# smartbedlight2.net
KiCad netlist of a schematic drawn in EAGLE
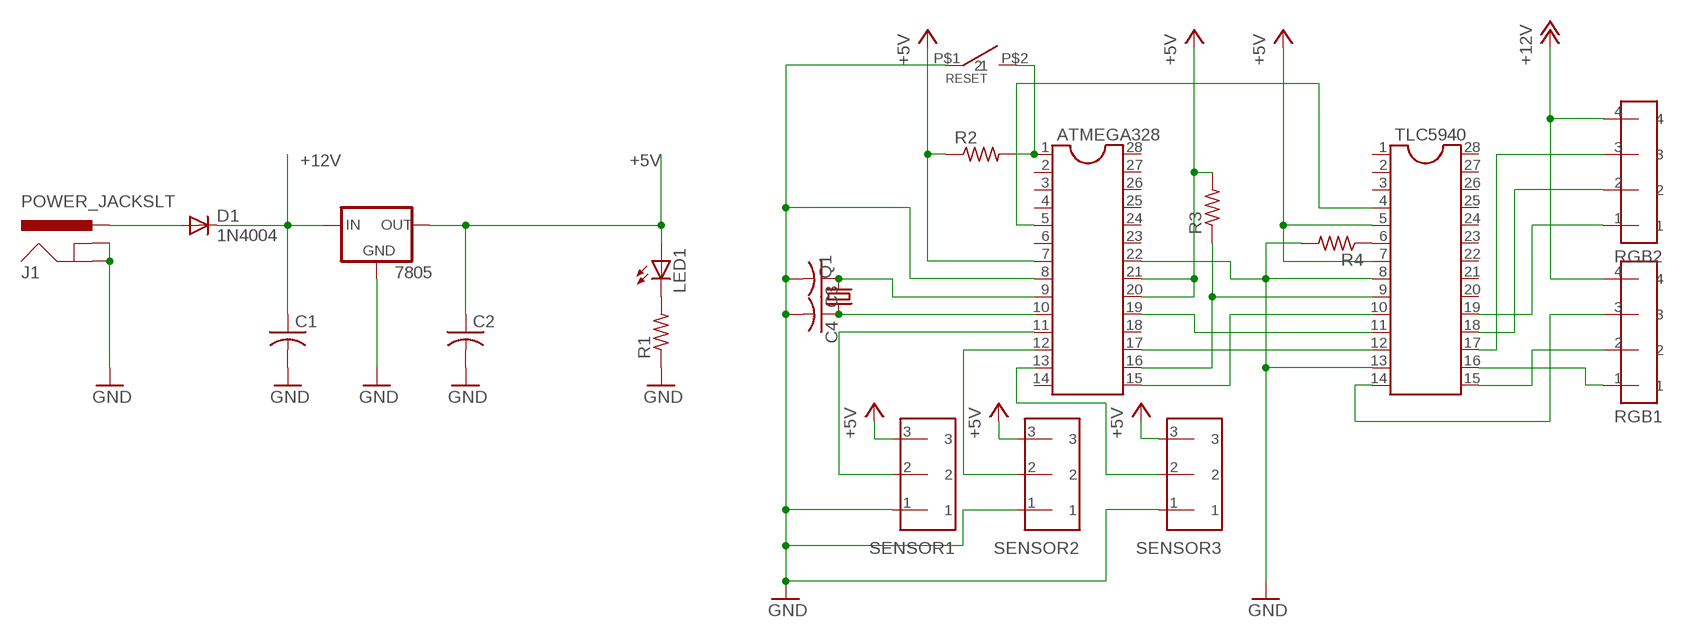
[diagram p0: schematic, sheet 1]

(export (version "E")
  (design (tool "Eeschema 10.0.6"))
  (components
    (comp (ref "7805")
      (value "V_REG_78XXSIDE")
      (footprint "eagle-import:78XXL")
      (libsource (lib "eagle-import") (part "V_REG_78XXSIDE"))
    )
    (comp (ref "ATMEGA328")
      (value "DIL28-3")
      (footprint "eagle-import:DIL28-3")
      (libsource (lib "eagle-import") (part "DIL28-3"))
    )
    (comp (ref "C1")
      (value "C-US025-030X050")
      (footprint "eagle-import:C025-030X050")
      (libsource (lib "eagle-import") (part "C-US025-030X050"))
    )
    (comp (ref "C2")
      (value "C-US025-030X050")
      (footprint "eagle-import:C025-030X050")
      (libsource (lib "eagle-import") (part "C-US025-030X050"))
    )
    (comp (ref "C3")
      (value "C-US025-025X050")
      (footprint "eagle-import:C025-025X050")
      (libsource (lib "eagle-import") (part "resistor_C-US025-025X050"))
    )
    (comp (ref "C4")
      (value "C-US025-025X050")
      (footprint "eagle-import:C025-025X050")
      (libsource (lib "eagle-import") (part "resistor_C-US025-025X050"))
    )
    (comp (ref "D1")
      (value "1N4004")
      (footprint "eagle-import:DO41-10")
      (libsource (lib "eagle-import") (part "1N4004"))
    )
    (comp (ref "J1")
      (value "POWER_JACKSLT")
      (footprint "eagle-import:POWER_JACK_SLOT")
      (libsource (lib "eagle-import") (part "POWER_JACKSLT"))
    )
    (comp (ref "LED1")
      (value "LED5MM")
      (footprint "eagle-import:LED5MM")
      (libsource (lib "eagle-import") (part "LED5MM"))
    )
    (comp (ref "Q1")
      (value "CRYSTALHC49U-V")
      (footprint "eagle-import:HC49U-V")
      (libsource (lib "eagle-import") (part "CRYSTALHC49U-V"))
    )
    (comp (ref "R1")
      (value "R-US_0204/7")
      (footprint "eagle-import:0204_7")
      (libsource (lib "eagle-import") (part "R-US_0204/7"))
    )
    (comp (ref "R2")
      (value "R-US_0207/10")
      (footprint "eagle-import:0207_10")
      (libsource (lib "eagle-import") (part "resistor_R-US_0207/10"))
    )
    (comp (ref "R3")
      (value "R-US_0207/10")
      (footprint "eagle-import:0207_10")
      (libsource (lib "eagle-import") (part "resistor_R-US_0207/10"))
    )
    (comp (ref "R4")
      (value "R-US_0207/10")
      (footprint "eagle-import:0207_10")
      (libsource (lib "eagle-import") (part "resistor_R-US_0207/10"))
    )
    (comp (ref "RESET")
      (value "TACK_SWITCH")
      (footprint "eagle-import:TACK_SWITCH")
      (libsource (lib "eagle-import") (part "TACK_SWITCH"))
    )
    (comp (ref "RGB1")
      (value "PINHEAD4")
      (footprint "eagle-import:PINHEAD4")
      (libsource (lib "eagle-import") (part "PINHEAD4"))
    )
    (comp (ref "RGB2")
      (value "PINHEAD4")
      (footprint "eagle-import:PINHEAD4")
      (libsource (lib "eagle-import") (part "PINHEAD4"))
    )
    (comp (ref "SENSOR1")
      (value "PINHEAD3")
      (footprint "eagle-import:PINHEAD")
      (libsource (lib "eagle-import") (part "PINHEAD3"))
    )
    (comp (ref "SENSOR2")
      (value "PINHEAD3")
      (footprint "eagle-import:PINHEAD")
      (libsource (lib "eagle-import") (part "PINHEAD3"))
    )
    (comp (ref "SENSOR3")
      (value "PINHEAD3")
      (footprint "eagle-import:PINHEAD")
      (libsource (lib "eagle-import") (part "PINHEAD3"))
    )
    (comp (ref "TLC5940")
      (value "DIL28-3")
      (footprint "eagle-import:DIL28-3")
      (libsource (lib "eagle-import") (part "DIL28-3"))
    )
  )
  (nets
    (net (code "1") (name "+5V") (class "Default")
      (node (ref "7805") (pin "OUT") (pinfunction "OUT_OUT") (pintype "output"))
      (node (ref "ATMEGA328") (pin "20") (pinfunction "20_20") (pintype "passive"))
      (node (ref "ATMEGA328") (pin "21") (pinfunction "21_21") (pintype "passive"))
      (node (ref "ATMEGA328") (pin "7") (pinfunction "7_7") (pintype "passive"))
      (node (ref "C2") (pin "1") (pinfunction "1_1") (pintype "passive"))
      (node (ref "LED1") (pin "A") (pinfunction "A_A") (pintype "passive"))
      (node (ref "R2") (pin "1") (pinfunction "1_1") (pintype "passive"))
      (node (ref "R3") (pin "2") (pinfunction "2_2") (pintype "passive"))
      (node (ref "SENSOR1") (pin "3") (pinfunction "3_3") (pintype "bidirectional"))
      (node (ref "SENSOR2") (pin "3") (pinfunction "3_3") (pintype "bidirectional"))
      (node (ref "SENSOR3") (pin "3") (pinfunction "3_3") (pintype "bidirectional"))
      (node (ref "TLC5940") (pin "5") (pinfunction "5_5") (pintype "passive"))
      (node (ref "TLC5940") (pin "7") (pinfunction "7_7") (pintype "passive"))
    )
    (net (code "2") (name "+12V") (class "Default")
      (node (ref "7805") (pin "IN") (pinfunction "IN_IN") (pintype "input"))
      (node (ref "C1") (pin "1") (pinfunction "1_1") (pintype "passive"))
      (node (ref "D1") (pin "C") (pinfunction "C_C") (pintype "passive"))
      (node (ref "RGB1") (pin "4") (pinfunction "4_4") (pintype "bidirectional"))
      (node (ref "RGB2") (pin "4") (pinfunction "4_4") (pintype "bidirectional"))
    )
    (net (code "3") (name "GND") (class "Default")
      (node (ref "7805") (pin "GND") (pinfunction "GND_GND") (pintype "input"))
      (node (ref "ATMEGA328") (pin "22") (pinfunction "22_22") (pintype "passive"))
      (node (ref "ATMEGA328") (pin "8") (pinfunction "8_8") (pintype "passive"))
      (node (ref "C1") (pin "2") (pinfunction "2_2") (pintype "passive"))
      (node (ref "C2") (pin "2") (pinfunction "2_2") (pintype "passive"))
      (node (ref "C3") (pin "2") (pinfunction "2_2") (pintype "passive"))
      (node (ref "C4") (pin "2") (pinfunction "2_2") (pintype "passive"))
      (node (ref "J1") (pin "GND@1") (pinfunction "GNDBREAK_GND@1") (pintype "bidirectional"))
      (node (ref "J1") (pin "GND@2") (pinfunction "GND_GND@2") (pintype "bidirectional"))
      (node (ref "R1") (pin "1") (pinfunction "1_1") (pintype "passive"))
      (node (ref "R4") (pin "2") (pinfunction "2_2") (pintype "passive"))
      (node (ref "RESET") (pin "P$1") (pinfunction "1_P$1") (pintype "bidirectional"))
      (node (ref "SENSOR1") (pin "1") (pinfunction "1_1") (pintype "bidirectional"))
      (node (ref "SENSOR2") (pin "1") (pinfunction "1_1") (pintype "bidirectional"))
      (node (ref "SENSOR3") (pin "1") (pinfunction "1_1") (pintype "bidirectional"))
      (node (ref "TLC5940") (pin "13") (pinfunction "13_13") (pintype "passive"))
      (node (ref "TLC5940") (pin "8") (pinfunction "8_8") (pintype "passive"))
    )
    (net (code "4") (name "Net-(ATMEGA328-Pad5)") (class "Default")
      (node (ref "ATMEGA328") (pin "5") (pinfunction "5_5") (pintype "passive"))
      (node (ref "TLC5940") (pin "4") (pinfunction "4_4") (pintype "passive"))
    )
    (net (code "5") (name "Net-(ATMEGA328-Pad9)") (class "Default")
      (node (ref "ATMEGA328") (pin "9") (pinfunction "9_9") (pintype "passive"))
      (node (ref "C3") (pin "1") (pinfunction "1_1") (pintype "passive"))
      (node (ref "Q1") (pin "2") (pinfunction "2_2") (pintype "passive"))
    )
    (net (code "6") (name "Net-(ATMEGA328-Pad10)") (class "Default")
      (node (ref "ATMEGA328") (pin "10") (pinfunction "10_10") (pintype "passive"))
      (node (ref "C4") (pin "1") (pinfunction "1_1") (pintype "passive"))
      (node (ref "Q1") (pin "1") (pinfunction "1_1") (pintype "passive"))
    )
    (net (code "7") (name "Net-(ATMEGA328-Pad11)") (class "Default")
      (node (ref "ATMEGA328") (pin "11") (pinfunction "11_11") (pintype "passive"))
      (node (ref "SENSOR1") (pin "2") (pinfunction "2_2") (pintype "bidirectional"))
    )
    (net (code "8") (name "Net-(ATMEGA328-Pad12)") (class "Default")
      (node (ref "ATMEGA328") (pin "12") (pinfunction "12_12") (pintype "passive"))
      (node (ref "SENSOR2") (pin "2") (pinfunction "2_2") (pintype "bidirectional"))
    )
    (net (code "9") (name "Net-(ATMEGA328-Pad13)") (class "Default")
      (node (ref "ATMEGA328") (pin "13") (pinfunction "13_13") (pintype "passive"))
      (node (ref "SENSOR3") (pin "2") (pinfunction "2_2") (pintype "bidirectional"))
    )
    (net (code "10") (name "Net-(ATMEGA328-Pad15)") (class "Default")
      (node (ref "ATMEGA328") (pin "15") (pinfunction "15_15") (pintype "passive"))
      (node (ref "TLC5940") (pin "10") (pinfunction "10_10") (pintype "passive"))
    )
    (net (code "11") (name "Net-(ATMEGA328-Pad16)") (class "Default")
      (node (ref "ATMEGA328") (pin "16") (pinfunction "16_16") (pintype "passive"))
      (node (ref "R3") (pin "1") (pinfunction "1_1") (pintype "passive"))
      (node (ref "TLC5940") (pin "9") (pinfunction "9_9") (pintype "passive"))
    )
    (net (code "12") (name "Net-(ATMEGA328-Pad17)") (class "Default")
      (node (ref "ATMEGA328") (pin "17") (pinfunction "17_17") (pintype "passive"))
      (node (ref "TLC5940") (pin "12") (pinfunction "12_12") (pintype "passive"))
    )
    (net (code "13") (name "Net-(ATMEGA328-Pad19)") (class "Default")
      (node (ref "ATMEGA328") (pin "19") (pinfunction "19_19") (pintype "passive"))
      (node (ref "TLC5940") (pin "11") (pinfunction "11_11") (pintype "passive"))
    )
    (net (code "14") (name "Net-(D1-PadA)") (class "Default")
      (node (ref "D1") (pin "A") (pinfunction "A_A") (pintype "passive"))
      (node (ref "J1") (pin "PWR") (pinfunction "PWR_PWR") (pintype "bidirectional"))
    )
    (net (code "15") (name "Net-(LED1-C)") (class "Default")
      (node (ref "LED1") (pin "K") (pinfunction "C_K") (pintype "passive"))
      (node (ref "R1") (pin "2") (pinfunction "2_2") (pintype "passive"))
    )
    (net (code "16") (name "Net-(R4-Pad1)") (class "Default")
      (node (ref "R4") (pin "1") (pinfunction "1_1") (pintype "passive"))
      (node (ref "TLC5940") (pin "6") (pinfunction "6_6") (pintype "passive"))
    )
    (net (code "17") (name "Net-(RESET-2)") (class "Default")
      (node (ref "ATMEGA328") (pin "1") (pinfunction "1_1") (pintype "passive"))
      (node (ref "R2") (pin "2") (pinfunction "2_2") (pintype "passive"))
      (node (ref "RESET") (pin "P$2") (pinfunction "2_P$2") (pintype "bidirectional"))
    )
    (net (code "18") (name "Net-(RGB1-Pad1)") (class "Default")
      (node (ref "RGB1") (pin "1") (pinfunction "1_1") (pintype "bidirectional"))
      (node (ref "TLC5940") (pin "16") (pinfunction "16_16") (pintype "passive"))
    )
    (net (code "19") (name "Net-(RGB1-Pad2)") (class "Default")
      (node (ref "RGB1") (pin "2") (pinfunction "2_2") (pintype "bidirectional"))
      (node (ref "TLC5940") (pin "15") (pinfunction "15_15") (pintype "passive"))
    )
    (net (code "20") (name "Net-(RGB1-Pad3)") (class "Default")
      (node (ref "RGB1") (pin "3") (pinfunction "3_3") (pintype "bidirectional"))
      (node (ref "TLC5940") (pin "14") (pinfunction "14_14") (pintype "passive"))
    )
    (net (code "21") (name "Net-(RGB2-Pad1)") (class "Default")
      (node (ref "RGB2") (pin "1") (pinfunction "1_1") (pintype "bidirectional"))
      (node (ref "TLC5940") (pin "19") (pinfunction "19_19") (pintype "passive"))
    )
    (net (code "22") (name "Net-(RGB2-Pad2)") (class "Default")
      (node (ref "RGB2") (pin "2") (pinfunction "2_2") (pintype "bidirectional"))
      (node (ref "TLC5940") (pin "18") (pinfunction "18_18") (pintype "passive"))
    )
    (net (code "23") (name "Net-(RGB2-Pad3)") (class "Default")
      (node (ref "RGB2") (pin "3") (pinfunction "3_3") (pintype "bidirectional"))
      (node (ref "TLC5940") (pin "17") (pinfunction "17_17") (pintype "passive"))
    )
    (net (code "24") (name "unconnected-(ATMEGA328-Pad2)") (class "Default")
      (node (ref "ATMEGA328") (pin "2") (pinfunction "2_2") (pintype "passive"))
    )
    (net (code "25") (name "unconnected-(ATMEGA328-Pad3)") (class "Default")
      (node (ref "ATMEGA328") (pin "3") (pinfunction "3_3") (pintype "passive"))
    )
    (net (code "26") (name "unconnected-(ATMEGA328-Pad4)") (class "Default")
      (node (ref "ATMEGA328") (pin "4") (pinfunction "4_4") (pintype "passive"))
    )
    (net (code "27") (name "unconnected-(ATMEGA328-Pad6)") (class "Default")
      (node (ref "ATMEGA328") (pin "6") (pinfunction "6_6") (pintype "passive"))
    )
    (net (code "28") (name "unconnected-(ATMEGA328-Pad14)") (class "Default")
      (node (ref "ATMEGA328") (pin "14") (pinfunction "14_14") (pintype "passive"))
    )
    (net (code "29") (name "unconnected-(ATMEGA328-Pad18)") (class "Default")
      (node (ref "ATMEGA328") (pin "18") (pinfunction "18_18") (pintype "passive"))
    )
    (net (code "30") (name "unconnected-(ATMEGA328-Pad23)") (class "Default")
      (node (ref "ATMEGA328") (pin "23") (pinfunction "23_23") (pintype "passive"))
    )
    (net (code "31") (name "unconnected-(ATMEGA328-Pad24)") (class "Default")
      (node (ref "ATMEGA328") (pin "24") (pinfunction "24_24") (pintype "passive"))
    )
    (net (code "32") (name "unconnected-(ATMEGA328-Pad25)") (class "Default")
      (node (ref "ATMEGA328") (pin "25") (pinfunction "25_25") (pintype "passive"))
    )
    (net (code "33") (name "unconnected-(ATMEGA328-Pad26)") (class "Default")
      (node (ref "ATMEGA328") (pin "26") (pinfunction "26_26") (pintype "passive"))
    )
    (net (code "34") (name "unconnected-(ATMEGA328-Pad27)") (class "Default")
      (node (ref "ATMEGA328") (pin "27") (pinfunction "27_27") (pintype "passive"))
    )
    (net (code "35") (name "unconnected-(ATMEGA328-Pad28)") (class "Default")
      (node (ref "ATMEGA328") (pin "28") (pinfunction "28_28") (pintype "passive"))
    )
    (net (code "36") (name "unconnected-(TLC5940-Pad1)") (class "Default")
      (node (ref "TLC5940") (pin "1") (pinfunction "1_1") (pintype "passive"))
    )
    (net (code "37") (name "unconnected-(TLC5940-Pad2)") (class "Default")
      (node (ref "TLC5940") (pin "2") (pinfunction "2_2") (pintype "passive"))
    )
    (net (code "38") (name "unconnected-(TLC5940-Pad3)") (class "Default")
      (node (ref "TLC5940") (pin "3") (pinfunction "3_3") (pintype "passive"))
    )
    (net (code "39") (name "unconnected-(TLC5940-Pad20)") (class "Default")
      (node (ref "TLC5940") (pin "20") (pinfunction "20_20") (pintype "passive"))
    )
    (net (code "40") (name "unconnected-(TLC5940-Pad21)") (class "Default")
      (node (ref "TLC5940") (pin "21") (pinfunction "21_21") (pintype "passive"))
    )
    (net (code "41") (name "unconnected-(TLC5940-Pad22)") (class "Default")
      (node (ref "TLC5940") (pin "22") (pinfunction "22_22") (pintype "passive"))
    )
    (net (code "42") (name "unconnected-(TLC5940-Pad23)") (class "Default")
      (node (ref "TLC5940") (pin "23") (pinfunction "23_23") (pintype "passive"))
    )
    (net (code "43") (name "unconnected-(TLC5940-Pad24)") (class "Default")
      (node (ref "TLC5940") (pin "24") (pinfunction "24_24") (pintype "passive"))
    )
    (net (code "44") (name "unconnected-(TLC5940-Pad25)") (class "Default")
      (node (ref "TLC5940") (pin "25") (pinfunction "25_25") (pintype "passive"))
    )
    (net (code "45") (name "unconnected-(TLC5940-Pad26)") (class "Default")
      (node (ref "TLC5940") (pin "26") (pinfunction "26_26") (pintype "passive"))
    )
    (net (code "46") (name "unconnected-(TLC5940-Pad27)") (class "Default")
      (node (ref "TLC5940") (pin "27") (pinfunction "27_27") (pintype "passive"))
    )
    (net (code "47") (name "unconnected-(TLC5940-Pad28)") (class "Default")
      (node (ref "TLC5940") (pin "28") (pinfunction "28_28") (pintype "passive"))
    )
  )
)
